# BP_Korevishe.net
KiCad netlist of a schematic drawn in EAGLE
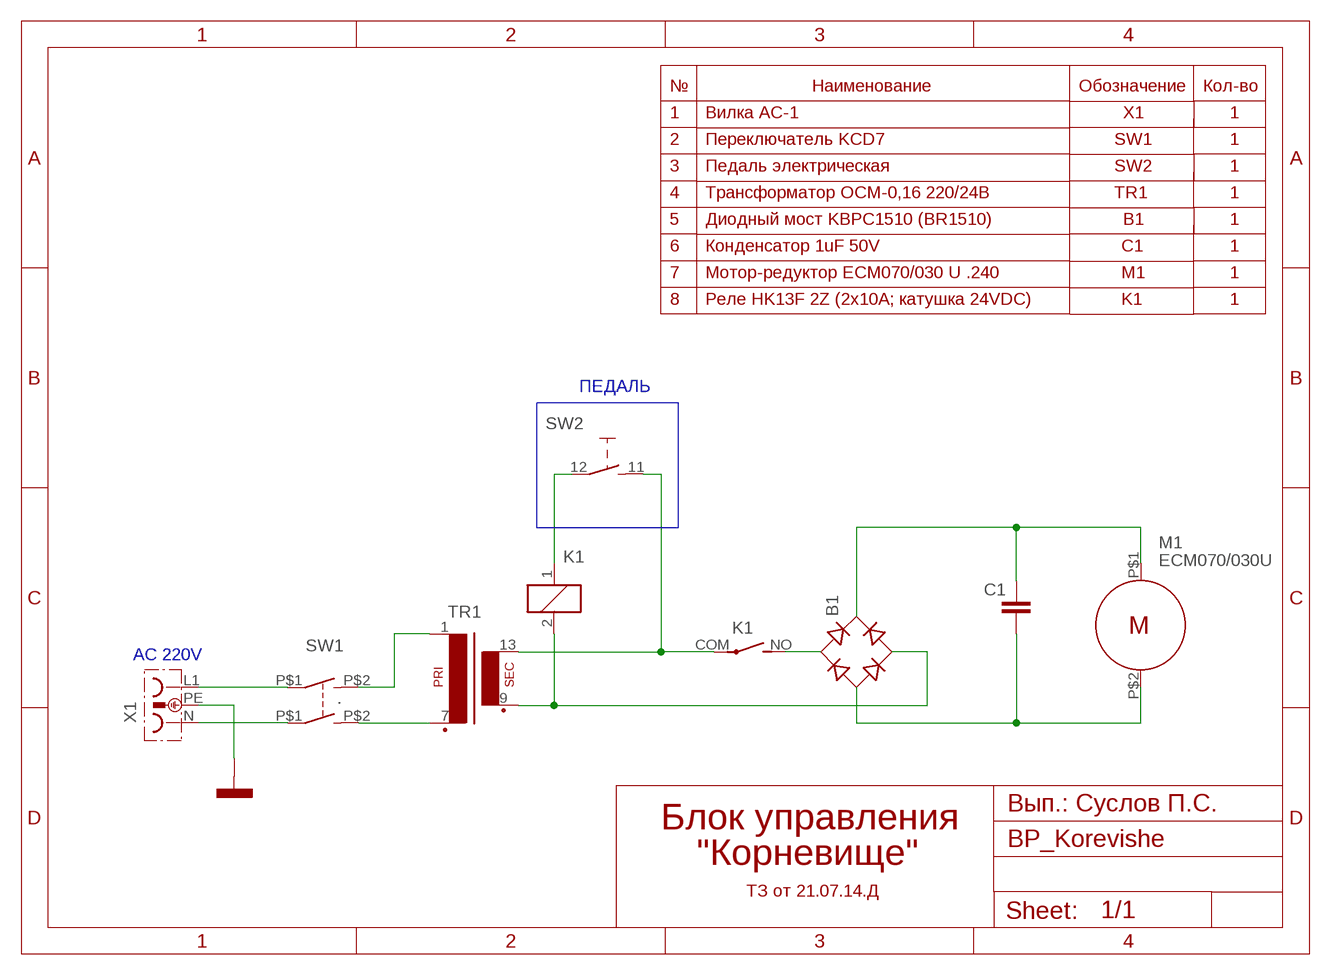
[diagram p0: schematic, sheet 1]

(export (version "E")
  (design (tool "Eeschema 10.0.6"))
  (components
    (comp (ref ".")
      (value "SCHLIESSER_ARBEITSKONTAKT")
      (footprint "eagle-import:1")
      (libsource (lib "eagle-import") (part "SCHLIESSER_ARBEITSKONTAKT"))
    )
    (comp (ref "B1")
      (value "B-DIL")
      (footprint "eagle-import:B-DIL")
      (libsource (lib "eagle-import") (part "B-DIL"))
    )
    (comp (ref "C1")
      (value "C-EU325-137X374")
      (footprint "eagle-import:C325-137X374")
      (libsource (lib "eagle-import") (part "C-EU325-137X374"))
    )
    (comp (ref "K1")
      (value "APF30212A")
      (footprint "eagle-import:APF30212A")
      (libsource (lib "eagle-import") (part "APF30212A"))
    )
    (comp (ref "M1")
      (value "ECM070/030U")
      (footprint "eagle-import:1")
      (libsource (lib "eagle-import") (part "MOTOR"))
    )
    (comp (ref "SW1")
      (value "SCHLIESSER_ARBEITSKONTAKT")
      (footprint "eagle-import:1")
      (libsource (lib "eagle-import") (part "SCHLIESSER_ARBEITSKONTAKT"))
    )
    (comp (ref "SW2")
      (value "SCHALTER_SCHLIESSER_HANDBETAETIGT")
      (footprint "eagle-import:KIPPSCHALTER_AUS")
      (libsource (lib "eagle-import") (part "SCHALTER_SCHLIESSER_HANDBETAETIGT"))
    )
    (comp (ref "TR1")
      (value "BV054-5381.0K")
      (footprint "eagle-import:EI54-18,8_16VA")
      (libsource (lib "eagle-import") (part "BV054-5381.0K"))
    )
    (comp (ref "X1")
      (value "STECKDOSE")
      (footprint "eagle-import:STECKDOSE")
      (libsource (lib "eagle-import") (part "STECKDOSE"))
    )
    (comp (ref "X2")
      (value "MASSE_ALLGEMEIN")
      (footprint "eagle-import:MASSE_ALLGEMEIN")
      (libsource (lib "eagle-import") (part "MASSE_ALLGEMEIN"))
    )
  )
  (nets
    (net (code "1") (name "Net-(.-3)") (class "Default")
      (node (ref ".") (pin "P$2") (pinfunction "3_P$2") (pintype "passive"))
      (node (ref "TR1") (pin "7") (pinfunction "P2_7") (pintype "passive"))
    )
    (net (code "2") (name "Net-(.-4)") (class "Default")
      (node (ref ".") (pin "P$1") (pinfunction "4_P$1") (pintype "passive"))
      (node (ref "X1") (pin "N") (pinfunction "N_N") (pintype "passive"))
    )
    (net (code "3") (name "Net-(K1B-P)") (class "Default")
      (node (ref "K1") (pin "COM") (pinfunction "P_COM") (pintype "passive"))
      (node (ref "SW2") (pin "11") (pinfunction "CS1_11") (pintype "passive"))
      (node (ref "TR1") (pin "13") (pinfunction "S4_13") (pintype "passive"))
    )
    (net (code "4") (name "Net-(K1B-S)") (class "Default")
      (node (ref "B1") (pin "AC1") (pinfunction "AC1_AC1") (pintype "passive"))
      (node (ref "K1") (pin "NO") (pinfunction "S_NO") (pintype "passive"))
    )
    (net (code "5") (name "Net-(M1-1)") (class "Default")
      (node (ref "B1") (pin "+") (pinfunction "+_+") (pintype "passive"))
      (node (ref "C1") (pin "1") (pinfunction "1_1") (pintype "passive"))
      (node (ref "M1") (pin "P$1") (pinfunction "1_P$1") (pintype "passive"))
    )
    (net (code "6") (name "Net-(M1-2)") (class "Default")
      (node (ref "B1") (pin "-") (pinfunction "-_-") (pintype "passive"))
      (node (ref "C1") (pin "2") (pinfunction "2_2") (pintype "passive"))
      (node (ref "M1") (pin "P$2") (pinfunction "2_P$2") (pintype "passive"))
    )
    (net (code "7") (name "Net-(SW1-3)") (class "Default")
      (node (ref "SW1") (pin "P$2") (pinfunction "3_P$2") (pintype "passive"))
      (node (ref "TR1") (pin "1") (pinfunction "P1_1") (pintype "passive"))
    )
    (net (code "8") (name "Net-(SW1-4)") (class "Default")
      (node (ref "SW1") (pin "P$1") (pinfunction "4_P$1") (pintype "passive"))
      (node (ref "X1") (pin "L1") (pinfunction "L1_L1") (pintype "passive"))
    )
    (net (code "9") (name "Net-(SW2-S1)") (class "Default")
      (node (ref "K1") (pin "1") (pinfunction "1_1") (pintype "passive"))
      (node (ref "SW2") (pin "12") (pinfunction "S1_12") (pintype "passive"))
    )
    (net (code "10") (name "Net-(TR1-S3)") (class "Default")
      (node (ref "B1") (pin "AC2") (pinfunction "AC2_AC2") (pintype "passive"))
      (node (ref "K1") (pin "2") (pinfunction "2_2") (pintype "passive"))
      (node (ref "TR1") (pin "9") (pinfunction "S3_9") (pintype "passive"))
    )
    (net (code "11") (name "Net-(X2-0V)") (class "Default")
      (node (ref "X1") (pin "PE") (pinfunction "PE_PE") (pintype "passive"))
      (node (ref "X2") (pin "1") (pinfunction "0V_1") (pintype "passive"))
    )
  )
)
